# SparkFun_Tranceiver_Breakout-nRF24L01.net
KiCad netlist of a schematic drawn in EAGLE
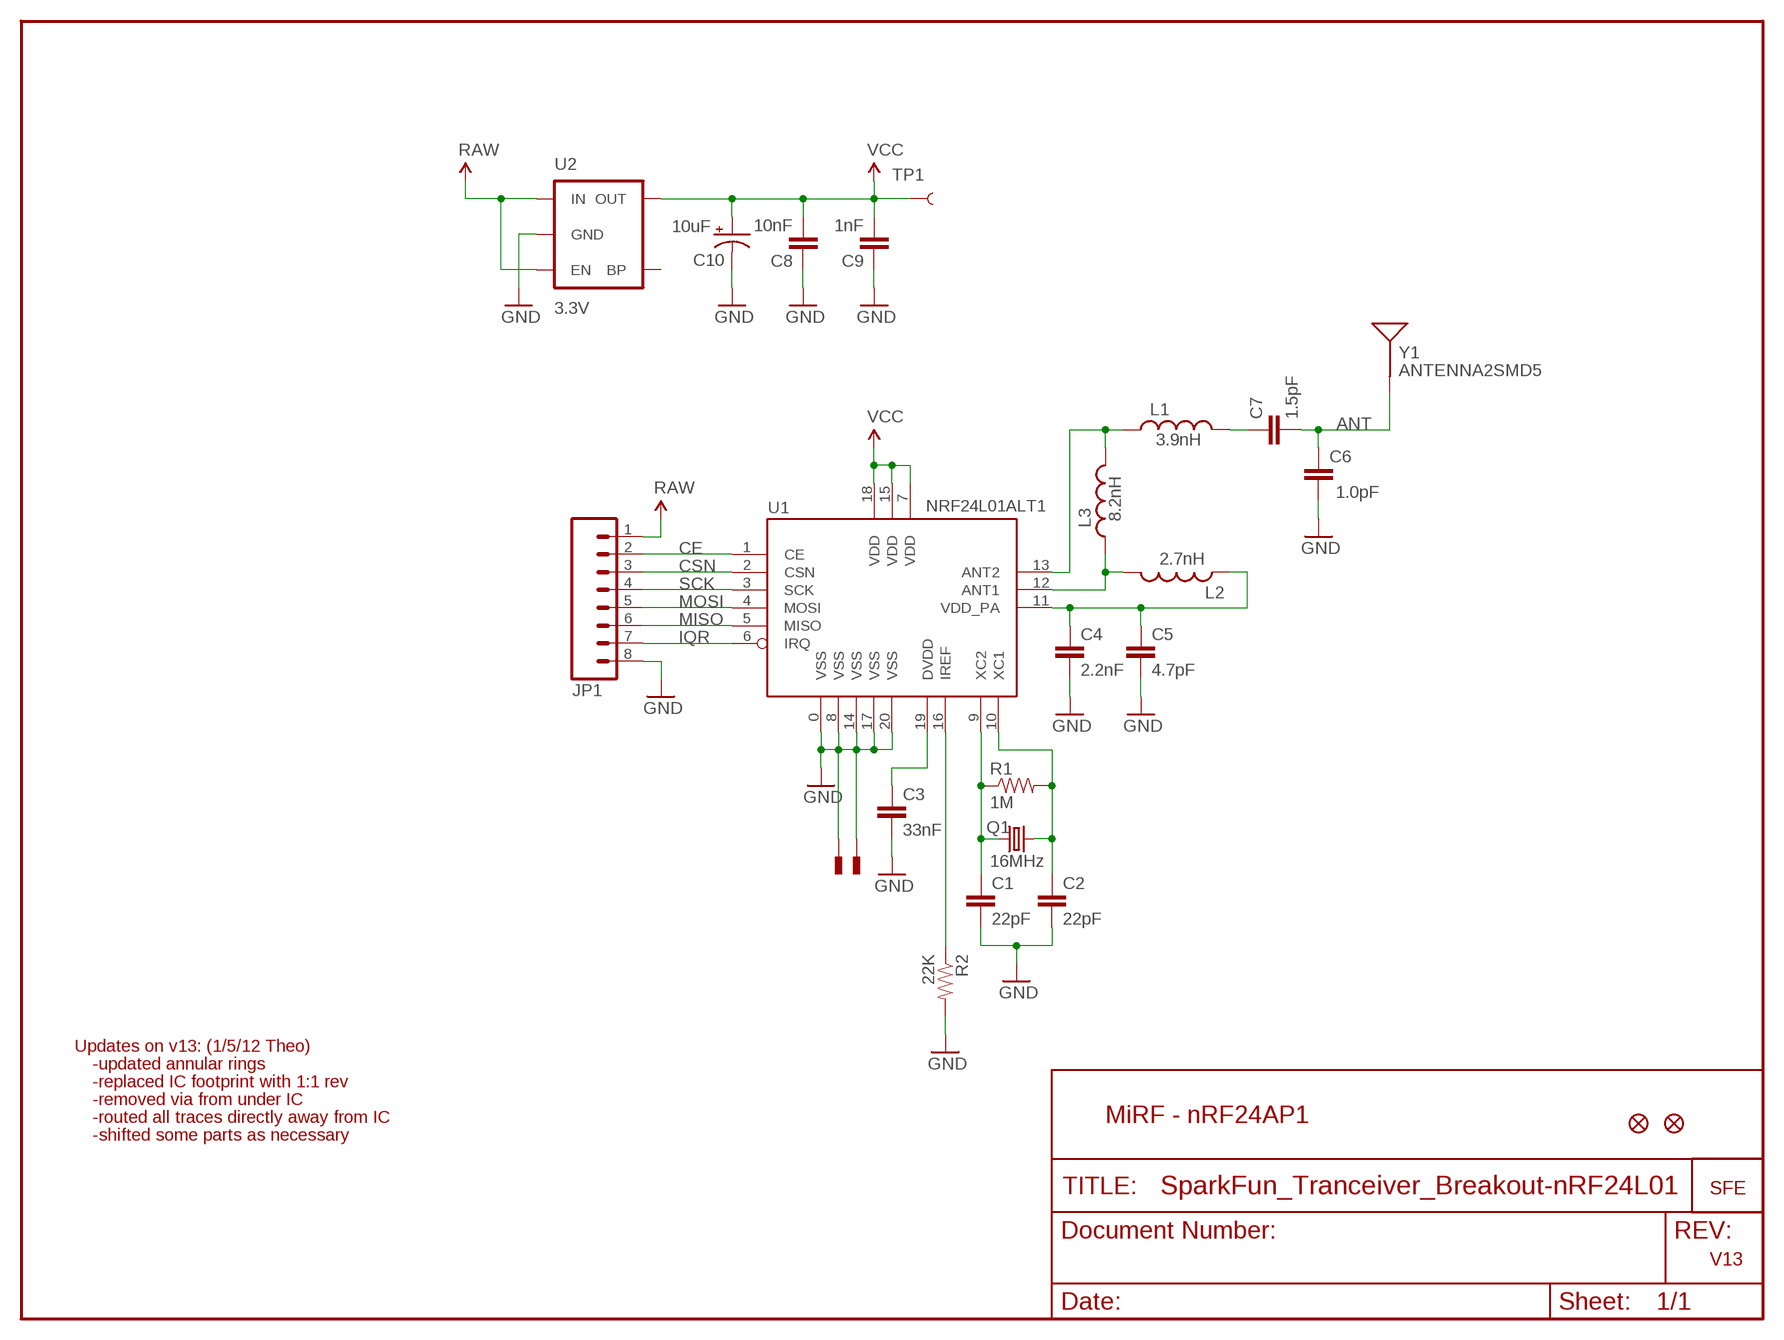
[diagram p0: schematic, sheet 1]

(export (version "E")
  (design (tool "Eeschema 10.0.6"))
  (components
    (comp (ref "C1")
      (value "22pF")
      (footprint "eagle-import:0402-CAP")
      (libsource (lib "eagle-import") (part "CAP0402-CAP"))
    )
    (comp (ref "C2")
      (value "22pF")
      (footprint "eagle-import:0402-CAP")
      (libsource (lib "eagle-import") (part "CAP0402-CAP"))
    )
    (comp (ref "C3")
      (value "33nF")
      (footprint "eagle-import:0402-CAP")
      (libsource (lib "eagle-import") (part "CAP0402-CAP"))
    )
    (comp (ref "C4")
      (value "2.2nF")
      (footprint "eagle-import:0402-CAP")
      (libsource (lib "eagle-import") (part "CAP0402-CAP"))
    )
    (comp (ref "C5")
      (value "4.7pF")
      (footprint "eagle-import:0402-CAP")
      (libsource (lib "eagle-import") (part "CAP0402-CAP"))
    )
    (comp (ref "C6")
      (value "1.0pF")
      (footprint "eagle-import:0402-CAP")
      (libsource (lib "eagle-import") (part "CAP0402-CAP"))
    )
    (comp (ref "C7")
      (value "1.5pF")
      (footprint "eagle-import:0402-CAP")
      (libsource (lib "eagle-import") (part "CAP0402-CAP"))
    )
    (comp (ref "C8")
      (value "10nF")
      (footprint "eagle-import:0402-CAP")
      (libsource (lib "eagle-import") (part "CAP0402-CAP"))
    )
    (comp (ref "C9")
      (value "1nF")
      (footprint "eagle-import:0402-CAP")
      (libsource (lib "eagle-import") (part "CAP0402-CAP"))
    )
    (comp (ref "C10")
      (value "10uF")
      (footprint "eagle-import:EIA3216")
      (libsource (lib "eagle-import") (part "CAP_POL1206"))
    )
    (comp (ref "JP1")
      (value "M081X08")
      (footprint "eagle-import:1X08")
      (libsource (lib "eagle-import") (part "M081X08"))
    )
    (comp (ref "JP2")
      (value "FIDUCIALUFIDUCIAL")
      (footprint "eagle-import:MICRO-FIDUCIAL")
      (libsource (lib "eagle-import") (part "FIDUCIALUFIDUCIAL"))
    )
    (comp (ref "JP3")
      (value "FIDUCIALUFIDUCIAL")
      (footprint "eagle-import:MICRO-FIDUCIAL")
      (libsource (lib "eagle-import") (part "FIDUCIALUFIDUCIAL"))
    )
    (comp (ref "L1")
      (value "3.9nH")
      (footprint "eagle-import:C0402")
      (libsource (lib "eagle-import") (part "INDUCTOR0402"))
    )
    (comp (ref "L2")
      (value "2.7nH")
      (footprint "eagle-import:C0402")
      (libsource (lib "eagle-import") (part "INDUCTOR0402"))
    )
    (comp (ref "L3")
      (value "8.2nH")
      (footprint "eagle-import:C0402")
      (libsource (lib "eagle-import") (part "INDUCTOR0402"))
    )
    (comp (ref "Q1")
      (value "16MHz")
      (footprint "eagle-import:CRYSTAL-SMD-5X3")
      (libsource (lib "eagle-import") (part "CRYSTAL5X3"))
    )
    (comp (ref "R1")
      (value "1M")
      (footprint "eagle-import:0402-RES")
      (libsource (lib "eagle-import") (part "RESISTOR0402-RES"))
    )
    (comp (ref "R2")
      (value "22K")
      (footprint "eagle-import:0402-RES")
      (libsource (lib "eagle-import") (part "RESISTOR0402-RES"))
    )
    (comp (ref "TP1")
      (value "TEST-POINT3X5")
      (footprint "eagle-import:PAD.03X.05")
      (libsource (lib "eagle-import") (part "TEST-POINT3X5"))
    )
    (comp (ref "U$1")
      (value "PAD")
      (footprint "eagle-import:PAD-0.008")
      (libsource (lib "eagle-import") (part "PAD"))
    )
    (comp (ref "U$4")
      (value "PAD")
      (footprint "eagle-import:PAD-0.008")
      (libsource (lib "eagle-import") (part "PAD"))
    )
    (comp (ref "U$5")
      (value "LOGO-SFENEW")
      (footprint "eagle-import:SFE-NEW-WEBLOGO")
      (libsource (lib "eagle-import") (part "LOGO-SFENEW"))
    )
    (comp (ref "U1")
      (value "NRF24L01ALT1")
      (footprint "eagle-import:QFN20_ALT1")
      (libsource (lib "eagle-import") (part "NRF24L01ALT1"))
    )
    (comp (ref "U2")
      (value "3.3V")
      (footprint "eagle-import:SOT23-5")
      (libsource (lib "eagle-import") (part "V_REG_LDOSMD"))
    )
    (comp (ref "Y1")
      (value "ANTENNA2SMD5")
      (footprint "eagle-import:ANTENNA-CHIP5")
      (libsource (lib "eagle-import") (part "ANTENNA2SMD5"))
    )
  )
  (nets
    (net (code "1") (name "/ANT") (class "Default")
      (node (ref "C6") (pin "2") (pinfunction "2_2") (pintype "passive"))
      (node (ref "C7") (pin "2") (pinfunction "2_2") (pintype "passive"))
      (node (ref "Y1") (pin "FEED") (pinfunction "SIGNAL_FEED") (pintype "bidirectional"))
    )
    (net (code "2") (name "/CE") (class "Default")
      (node (ref "JP1") (pin "2") (pinfunction "2_2") (pintype "passive"))
      (node (ref "U1") (pin "1") (pinfunction "CE_1") (pintype "input"))
    )
    (net (code "3") (name "/CSN") (class "Default")
      (node (ref "JP1") (pin "3") (pinfunction "3_3") (pintype "passive"))
      (node (ref "U1") (pin "2") (pinfunction "CSN_2") (pintype "input"))
    )
    (net (code "4") (name "/IQR") (class "Default")
      (node (ref "JP1") (pin "7") (pinfunction "7_7") (pintype "passive"))
      (node (ref "U1") (pin "6") (pinfunction "IRQ_6") (pintype "output"))
    )
    (net (code "5") (name "/MISO") (class "Default")
      (node (ref "JP1") (pin "6") (pinfunction "6_6") (pintype "passive"))
      (node (ref "U1") (pin "5") (pinfunction "MISO_5") (pintype "output"))
    )
    (net (code "6") (name "/MOSI") (class "Default")
      (node (ref "JP1") (pin "5") (pinfunction "5_5") (pintype "passive"))
      (node (ref "U1") (pin "4") (pinfunction "MOSI_4") (pintype "input"))
    )
    (net (code "7") (name "/SCK") (class "Default")
      (node (ref "JP1") (pin "4") (pinfunction "4_4") (pintype "passive"))
      (node (ref "U1") (pin "3") (pinfunction "SCK_3") (pintype "input"))
    )
    (net (code "8") (name "GND") (class "Default")
      (node (ref "C1") (pin "2") (pinfunction "2_2") (pintype "passive"))
      (node (ref "C10") (pin "C") (pinfunction "-_C") (pintype "passive"))
      (node (ref "C2") (pin "2") (pinfunction "2_2") (pintype "passive"))
      (node (ref "C3") (pin "2") (pinfunction "2_2") (pintype "passive"))
      (node (ref "C4") (pin "2") (pinfunction "2_2") (pintype "passive"))
      (node (ref "C5") (pin "2") (pinfunction "2_2") (pintype "passive"))
      (node (ref "C6") (pin "1") (pinfunction "1_1") (pintype "passive"))
      (node (ref "C8") (pin "1") (pinfunction "1_1") (pintype "passive"))
      (node (ref "C9") (pin "1") (pinfunction "1_1") (pintype "passive"))
      (node (ref "JP1") (pin "8") (pinfunction "8_8") (pintype "passive"))
      (node (ref "R2") (pin "2") (pinfunction "2_2") (pintype "passive"))
      (node (ref "U$1") (pin "P$1") (pinfunction "P$1_P$1") (pintype "bidirectional"))
      (node (ref "U$4") (pin "P$1") (pinfunction "P$1_P$1") (pintype "bidirectional"))
      (node (ref "U1") (pin "0") (pinfunction "VSS_0") (pintype "power_in"))
      (node (ref "U1") (pin "14") (pinfunction "VSS_14") (pintype "power_in"))
      (node (ref "U1") (pin "17") (pinfunction "VSS_17") (pintype "power_in"))
      (node (ref "U1") (pin "20") (pinfunction "VSS_20") (pintype "power_in"))
      (node (ref "U1") (pin "8") (pinfunction "VSS_8") (pintype "power_in"))
      (node (ref "U2") (pin "2") (pinfunction "GND_2") (pintype "input"))
    )
    (net (code "9") (name "Net-(C7-Pad1)") (class "Default")
      (node (ref "C7") (pin "1") (pinfunction "1_1") (pintype "passive"))
      (node (ref "L1") (pin "2") (pinfunction "2_2") (pintype "passive"))
    )
    (net (code "10") (name "Net-(Q1-2)") (class "Default")
      (node (ref "C2") (pin "1") (pinfunction "1_1") (pintype "passive"))
      (node (ref "Q1") (pin "3") (pinfunction "2_3") (pintype "passive"))
      (node (ref "R1") (pin "2") (pinfunction "2_2") (pintype "passive"))
      (node (ref "U1") (pin "10") (pinfunction "XC1_10") (pintype "input"))
    )
    (net (code "11") (name "Net-(U1-ANT1)") (class "Default")
      (node (ref "L2") (pin "2") (pinfunction "2_2") (pintype "passive"))
      (node (ref "L3") (pin "1") (pinfunction "1_1") (pintype "passive"))
      (node (ref "U1") (pin "12") (pinfunction "ANT1_12") (pintype "output"))
    )
    (net (code "12") (name "Net-(U1-ANT2)") (class "Default")
      (node (ref "L1") (pin "1") (pinfunction "1_1") (pintype "passive"))
      (node (ref "L3") (pin "2") (pinfunction "2_2") (pintype "passive"))
      (node (ref "U1") (pin "13") (pinfunction "ANT2_13") (pintype "output"))
    )
    (net (code "13") (name "Net-(U1-DVDD)") (class "Default")
      (node (ref "C3") (pin "1") (pinfunction "1_1") (pintype "passive"))
      (node (ref "U1") (pin "19") (pinfunction "DVDD_19") (pintype "power_in"))
    )
    (net (code "14") (name "Net-(U1-IREF)") (class "Default")
      (node (ref "R2") (pin "1") (pinfunction "1_1") (pintype "passive"))
      (node (ref "U1") (pin "16") (pinfunction "IREF_16") (pintype "input"))
    )
    (net (code "15") (name "Net-(U1-VDD_PA)") (class "Default")
      (node (ref "C4") (pin "1") (pinfunction "1_1") (pintype "passive"))
      (node (ref "C5") (pin "1") (pinfunction "1_1") (pintype "passive"))
      (node (ref "L2") (pin "1") (pinfunction "1_1") (pintype "passive"))
      (node (ref "U1") (pin "11") (pinfunction "VDD_PA_11") (pintype "power_in"))
    )
    (net (code "16") (name "Net-(U1-XC2)") (class "Default")
      (node (ref "C1") (pin "1") (pinfunction "1_1") (pintype "passive"))
      (node (ref "Q1") (pin "1") (pinfunction "1_1") (pintype "passive"))
      (node (ref "R1") (pin "1") (pinfunction "1_1") (pintype "passive"))
      (node (ref "U1") (pin "9") (pinfunction "XC2_9") (pintype "input"))
    )
    (net (code "17") (name "RAW") (class "Default")
      (node (ref "JP1") (pin "1") (pinfunction "1_1") (pintype "passive"))
      (node (ref "U2") (pin "1") (pinfunction "IN_1") (pintype "input"))
      (node (ref "U2") (pin "3") (pinfunction "EN_3") (pintype "input"))
    )
    (net (code "18") (name "VCC") (class "Default")
      (node (ref "C10") (pin "A") (pinfunction "+_A") (pintype "passive"))
      (node (ref "C8") (pin "2") (pinfunction "2_2") (pintype "passive"))
      (node (ref "C9") (pin "2") (pinfunction "2_2") (pintype "passive"))
      (node (ref "TP1") (pin "P$1") (pinfunction "1_P$1") (pintype "bidirectional"))
      (node (ref "U1") (pin "15") (pinfunction "VDD_15") (pintype "power_in"))
      (node (ref "U1") (pin "18") (pinfunction "VDD_18") (pintype "power_in"))
      (node (ref "U1") (pin "7") (pinfunction "VDD_7") (pintype "power_in"))
      (node (ref "U2") (pin "5") (pinfunction "OUT_5") (pintype "passive"))
    )
    (net (code "19") (name "unconnected-(U2-BP-Pad4)") (class "Default")
      (node (ref "U2") (pin "4") (pinfunction "BP_4") (pintype "input"))
    )
  )
)
